# DS2482_1_Wire_Controller_Rev_C.net
KiCad netlist of a schematic drawn in EAGLE
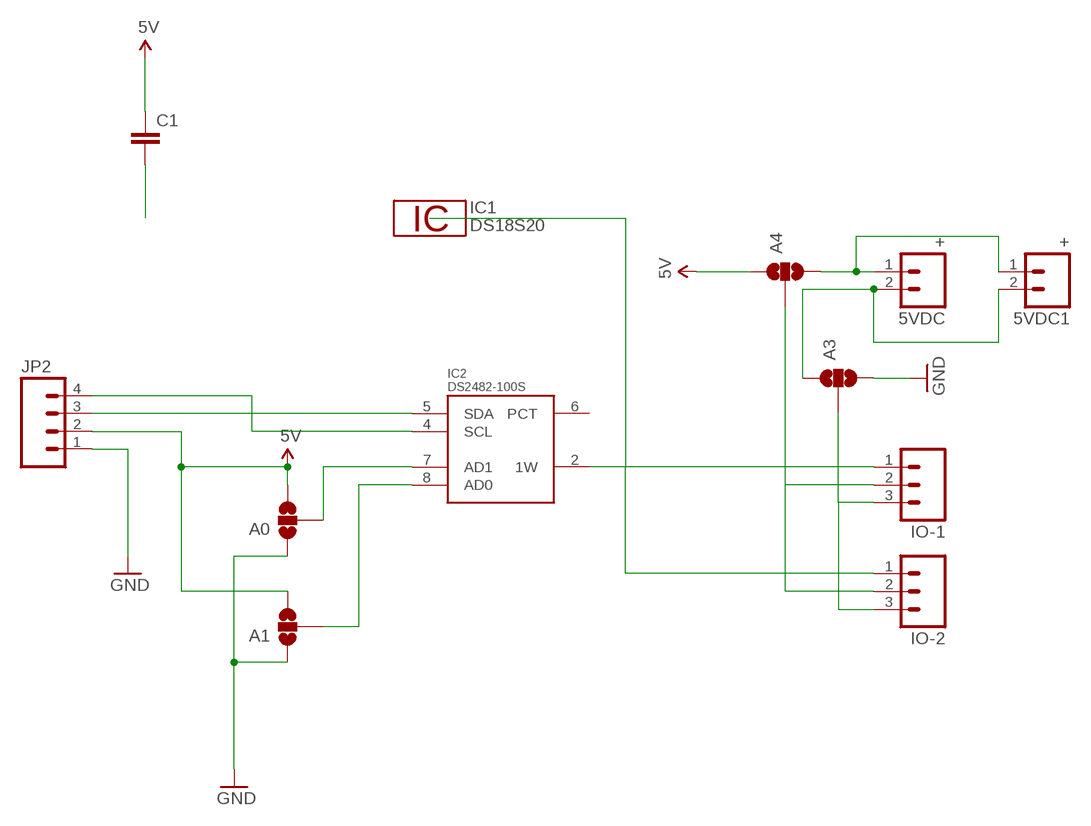
[diagram p0: schematic, sheet 1]

(export (version "E")
  (design (tool "Eeschema 10.0.6"))
  (components
    (comp (ref "5VDC")
      (value "+")
      (footprint "eagle-import:1X02")
      (libsource (lib "eagle-import") (part "M02PTH"))
    )
    (comp (ref "5VDC1")
      (value "+")
      (footprint "eagle-import:1X02")
      (libsource (lib "eagle-import") (part "M02PTH"))
    )
    (comp (ref "A0")
      (value "SOLDERJUMPER_2WAYS")
      (footprint "eagle-import:SJ_3")
      (libsource (lib "eagle-import") (part "SOLDERJUMPER_2WAYS"))
    )
    (comp (ref "A1")
      (value "SOLDERJUMPER_2WAYS")
      (footprint "eagle-import:SJ_3")
      (libsource (lib "eagle-import") (part "SOLDERJUMPER_2WAYS"))
    )
    (comp (ref "A3")
      (value "SOLDERJUMPER_2WAYS")
      (footprint "eagle-import:SJ_3")
      (libsource (lib "eagle-import") (part "SOLDERJUMPER_2WAYS"))
    )
    (comp (ref "A4")
      (value "SOLDERJUMPER_2WAYS")
      (footprint "eagle-import:SJ_3")
      (libsource (lib "eagle-import") (part "SOLDERJUMPER_2WAYS"))
    )
    (comp (ref "C1")
      (value "CAPPTH2")
      (footprint "eagle-import:CAP-PTH-SMALL2")
      (libsource (lib "eagle-import") (part "CAPPTH2"))
    )
    (comp (ref "IC1")
      (value "DS18S20")
      (footprint "eagle-import:TO92-")
      (libsource (lib "eagle-import") (part "DS18S20"))
    )
    (comp (ref "IC2")
      (value "DS2482-100S")
      (footprint "eagle-import:SO08")
      (libsource (lib "eagle-import") (part "DS2482-100S"))
    )
    (comp (ref "IO-1")
      (value "M03PTH")
      (footprint "eagle-import:1X03")
      (libsource (lib "eagle-import") (part "M03PTH"))
    )
    (comp (ref "IO-2")
      (value "M03PTH")
      (footprint "eagle-import:1X03")
      (libsource (lib "eagle-import") (part "M03PTH"))
    )
    (comp (ref "JP2")
      (value "M04PTH")
      (footprint "eagle-import:1X04")
      (libsource (lib "eagle-import") (part "M04PTH"))
    )
  )
  (nets
    (net (code "1") (name "5V") (class "Default")
      (node (ref "A0") (pin "3") (pinfunction "3_3") (pintype "passive"))
      (node (ref "A1") (pin "3") (pinfunction "3_3") (pintype "passive"))
      (node (ref "A4") (pin "1") (pinfunction "1_1") (pintype "passive"))
      (node (ref "C1") (pin "1") (pinfunction "1_1") (pintype "passive"))
      (node (ref "JP2") (pin "2") (pinfunction "2_2") (pintype "passive"))
    )
    (net (code "2") (name "GND") (class "Default")
      (node (ref "A0") (pin "1") (pinfunction "1_1") (pintype "passive"))
      (node (ref "A1") (pin "1") (pinfunction "1_1") (pintype "passive"))
      (node (ref "A3") (pin "3") (pinfunction "3_3") (pintype "passive"))
      (node (ref "JP2") (pin "1") (pinfunction "1_1") (pintype "passive"))
    )
    (net (code "3") (name "Net-(5VDC-Pad1)") (class "Default")
      (node (ref "5VDC") (pin "1") (pinfunction "1_1") (pintype "passive"))
      (node (ref "5VDC1") (pin "1") (pinfunction "1_1") (pintype "passive"))
      (node (ref "A4") (pin "3") (pinfunction "3_3") (pintype "passive"))
    )
    (net (code "4") (name "Net-(5VDC-Pad2)") (class "Default")
      (node (ref "5VDC") (pin "2") (pinfunction "2_2") (pintype "passive"))
      (node (ref "5VDC1") (pin "2") (pinfunction "2_2") (pintype "passive"))
      (node (ref "A3") (pin "1") (pinfunction "1_1") (pintype "passive"))
    )
    (net (code "5") (name "Net-(A3-Pad2)") (class "Default")
      (node (ref "A3") (pin "2") (pinfunction "2_2") (pintype "passive"))
      (node (ref "IO-1") (pin "3") (pinfunction "3_3") (pintype "passive"))
      (node (ref "IO-2") (pin "3") (pinfunction "3_3") (pintype "passive"))
    )
    (net (code "6") (name "Net-(A4-Pad2)") (class "Default")
      (node (ref "A4") (pin "2") (pinfunction "2_2") (pintype "passive"))
      (node (ref "IO-1") (pin "2") (pinfunction "2_2") (pintype "passive"))
      (node (ref "IO-2") (pin "2") (pinfunction "2_2") (pintype "passive"))
    )
    (net (code "7") (name "Net-(IC2A-1W)") (class "Default")
      (node (ref "IC2") (pin "2") (pinfunction "1W_2") (pintype "open_collector"))
      (node (ref "IO-1") (pin "1") (pinfunction "1_1") (pintype "passive"))
      (node (ref "IO-2") (pin "1") (pinfunction "1_1") (pintype "passive"))
    )
    (net (code "8") (name "Net-(IC2A-AD0)") (class "Default")
      (node (ref "A1") (pin "2") (pinfunction "2_2") (pintype "passive"))
      (node (ref "IC2") (pin "8") (pinfunction "AD0_8") (pintype "input"))
    )
    (net (code "9") (name "Net-(IC2A-AD1)") (class "Default")
      (node (ref "A0") (pin "2") (pinfunction "2_2") (pintype "passive"))
      (node (ref "IC2") (pin "7") (pinfunction "AD1_7") (pintype "input"))
    )
    (net (code "10") (name "Net-(IC2A-SCL)") (class "Default")
      (node (ref "IC2") (pin "4") (pinfunction "SCL_4") (pintype "input"))
      (node (ref "JP2") (pin "4") (pinfunction "4_4") (pintype "passive"))
    )
    (net (code "11") (name "Net-(IC2A-SDA)") (class "Default")
      (node (ref "IC2") (pin "5") (pinfunction "SDA_5") (pintype "bidirectional"))
      (node (ref "JP2") (pin "3") (pinfunction "3_3") (pintype "passive"))
    )
    (net (code "12") (name "unconnected-(C1-Pad2)") (class "Default")
      (node (ref "C1") (pin "2") (pinfunction "2_2") (pintype "passive"))
    )
    (net (code "13") (name "unconnected-(IC2A-PCT-Pad6)") (class "Default")
      (node (ref "IC2") (pin "6") (pinfunction "PCT_6") (pintype "output"))
    )
  )
)
